# Final_NOEC_KosikC.net
KiCad netlist of a schematic drawn in EAGLE
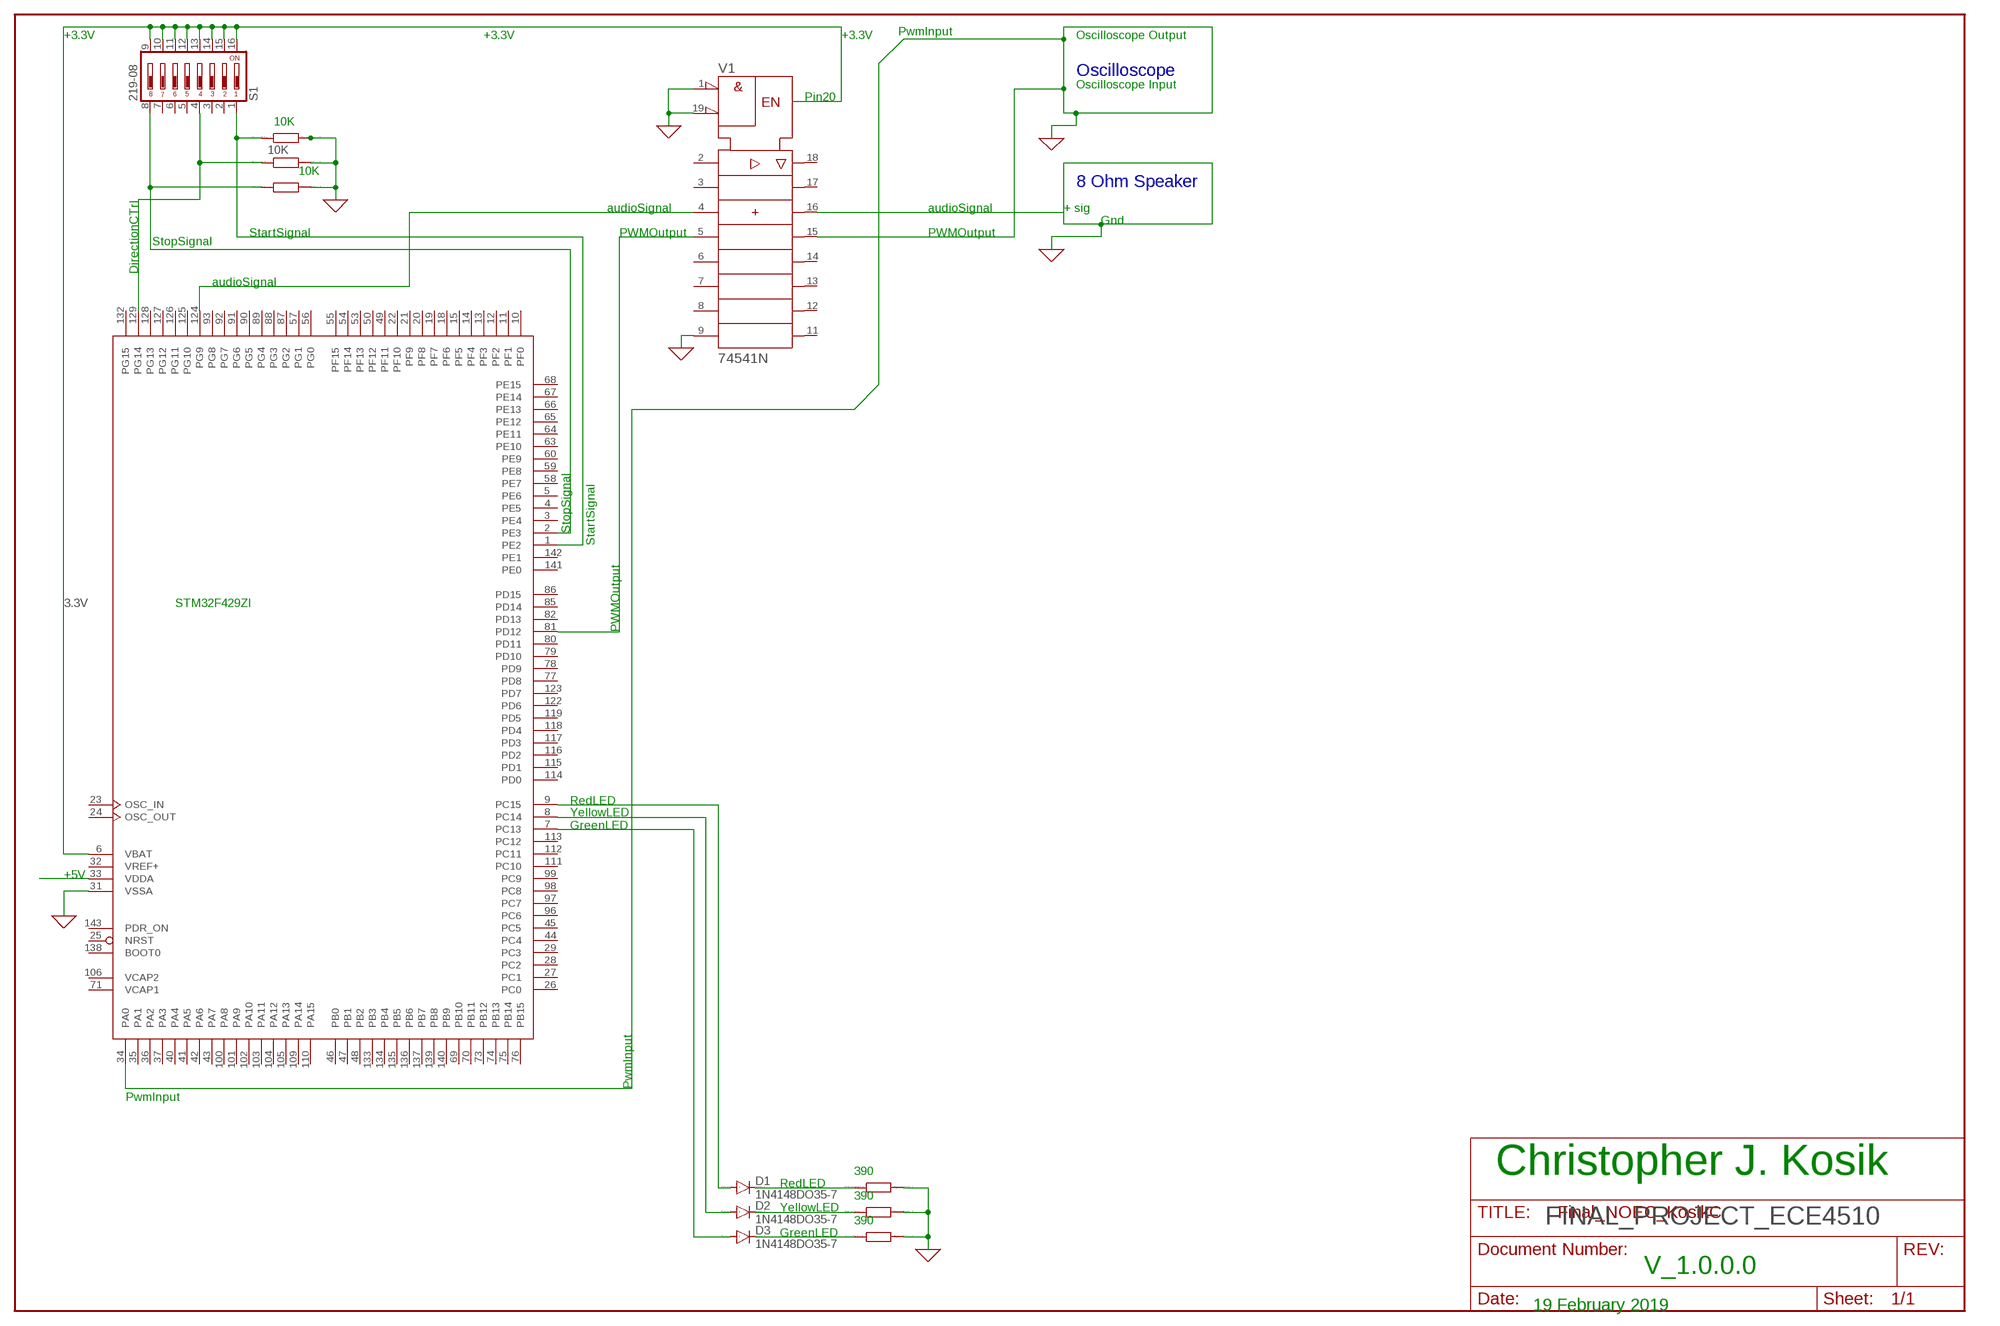
[diagram p0: schematic, sheet 1]

(export (version "E")
  (design (tool "Eeschema 10.0.6"))
  (components
    (comp (ref "D1")
      (value "1N4148DO35-7")
      (footprint "eagle-import:DO35-7")
      (libsource (lib "eagle-import") (part "1N4148DO35-7"))
    )
    (comp (ref "D2")
      (value "1N4148DO35-7")
      (footprint "eagle-import:DO35-7")
      (libsource (lib "eagle-import") (part "1N4148DO35-7"))
    )
    (comp (ref "D3")
      (value "1N4148DO35-7")
      (footprint "eagle-import:DO35-7")
      (libsource (lib "eagle-import") (part "1N4148DO35-7"))
    )
    (comp (ref "IC1")
      (value "STM32F429ZGT")
      (footprint "eagle-import:LQFP144")
      (libsource (lib "eagle-import") (part "STM32F429ZTG"))
    )
    (comp (ref "R1")
      (value "10K")
      (footprint "eagle-import:R0805")
      (libsource (lib "eagle-import") (part "R"))
    )
    (comp (ref "R2") (value "R") (footprint "eagle-import:R0805") (libsource (lib "eagle-import") (part "R")))
    (comp (ref "R3") (value "R") (footprint "eagle-import:R0805") (libsource (lib "eagle-import") (part "R")))
    (comp (ref "R4") (value "R") (footprint "eagle-import:R0805") (libsource (lib "eagle-import") (part "R")))
    (comp (ref "R5") (value "R") (footprint "eagle-import:R0805") (libsource (lib "eagle-import") (part "R")))
    (comp (ref "R6") (value "R") (footprint "eagle-import:R0805") (libsource (lib "eagle-import") (part "R")))
    (comp (ref "S1")
      (value "219-08")
      (footprint "eagle-import:CTS-219-08")
      (libsource (lib "eagle-import") (part "219-08"))
    )
    (comp (ref "V1")
      (value "74541N")
      (footprint "eagle-import:DIL20")
      (libsource (lib "eagle-import") (part "74541N"))
    )
  )
  (nets
    (net (code "1") (name "/3.3V") (class "Default")
      (node (ref "IC1") (pin "6") (pinfunction "VBAT_6") (pintype "power_in"))
      (node (ref "S1") (pin "10") (pinfunction "10_10") (pintype "passive"))
      (node (ref "S1") (pin "11") (pinfunction "11_11") (pintype "passive"))
      (node (ref "S1") (pin "12") (pinfunction "12_12") (pintype "passive"))
      (node (ref "S1") (pin "13") (pinfunction "13_13") (pintype "passive"))
      (node (ref "S1") (pin "14") (pinfunction "14_14") (pintype "passive"))
      (node (ref "S1") (pin "15") (pinfunction "15_15") (pintype "passive"))
      (node (ref "S1") (pin "16") (pinfunction "16_16") (pintype "passive"))
      (node (ref "S1") (pin "9") (pinfunction "9_9") (pintype "passive"))
    )
    (net (code "2") (name "/VCAP1") (class "Default")
      (node (ref "IC1") (pin "71") (pinfunction "VCAP1_71") (pintype "power_in"))
    )
    (net (code "3") (name "/VCAP2") (class "Default")
      (node (ref "IC1") (pin "106") (pinfunction "VCAP2_106") (pintype "power_in"))
    )
    (net (code "4") (name "/VREF+") (class "Default")
      (node (ref "IC1") (pin "32") (pinfunction "VREF+_32") (pintype "power_in"))
    )
    (net (code "5") (name "GND") (class "Default")
      (node (ref "IC1") (pin "31") (pinfunction "VSSA_31") (pintype "power_in"))
      (node (ref "IC1") (pin "34") (pinfunction "PA0_34") (pintype "bidirectional"))
      (node (ref "R1") (pin "2") (pinfunction "2_2") (pintype "passive"))
      (node (ref "R2") (pin "2") (pinfunction "2_2") (pintype "passive"))
      (node (ref "R3") (pin "2") (pinfunction "2_2") (pintype "passive"))
      (node (ref "R4") (pin "2") (pinfunction "2_2") (pintype "passive"))
      (node (ref "R5") (pin "2") (pinfunction "2_2") (pintype "passive"))
      (node (ref "R6") (pin "2") (pinfunction "2_2") (pintype "passive"))
      (node (ref "V1") (pin "1") (pinfunction "~{G1}_1") (pintype "input"))
      (node (ref "V1") (pin "15") (pinfunction "Y4_15") (pintype "tri_state"))
      (node (ref "V1") (pin "16") (pinfunction "Y3_16") (pintype "tri_state"))
      (node (ref "V1") (pin "19") (pinfunction "~{G2}_19") (pintype "input"))
      (node (ref "V1") (pin "9") (pinfunction "A8_9") (pintype "input"))
    )
    (net (code "6") (name "Net-(D1-PadC)") (class "Default")
      (node (ref "D1") (pin "C") (pinfunction "C_C") (pintype "passive"))
      (node (ref "R4") (pin "1") (pinfunction "1_1") (pintype "passive"))
    )
    (net (code "7") (name "Net-(D2-PadC)") (class "Default")
      (node (ref "D2") (pin "C") (pinfunction "C_C") (pintype "passive"))
      (node (ref "R5") (pin "1") (pinfunction "1_1") (pintype "passive"))
    )
    (net (code "8") (name "Net-(D3-PadC)") (class "Default")
      (node (ref "D3") (pin "C") (pinfunction "C_C") (pintype "passive"))
      (node (ref "R6") (pin "1") (pinfunction "1_1") (pintype "passive"))
    )
    (net (code "9") (name "Net-(IC1A-PC13)") (class "Default")
      (node (ref "D3") (pin "A") (pinfunction "A_A") (pintype "passive"))
      (node (ref "IC1") (pin "7") (pinfunction "PC13_7") (pintype "bidirectional"))
    )
    (net (code "10") (name "Net-(IC1A-PC14)") (class "Default")
      (node (ref "D2") (pin "A") (pinfunction "A_A") (pintype "passive"))
      (node (ref "IC1") (pin "8") (pinfunction "PC14_8") (pintype "bidirectional"))
    )
    (net (code "11") (name "Net-(IC1A-PC15)") (class "Default")
      (node (ref "D1") (pin "A") (pinfunction "A_A") (pintype "passive"))
      (node (ref "IC1") (pin "9") (pinfunction "PC15_9") (pintype "bidirectional"))
    )
    (net (code "12") (name "Net-(IC1A-PD12)") (class "Default")
      (node (ref "IC1") (pin "81") (pinfunction "PD12_81") (pintype "bidirectional"))
      (node (ref "V1") (pin "5") (pinfunction "A4_5") (pintype "input"))
    )
    (net (code "13") (name "Net-(IC1A-PE2)") (class "Default")
      (node (ref "IC1") (pin "1") (pinfunction "PE2_1") (pintype "bidirectional"))
      (node (ref "R1") (pin "1") (pinfunction "1_1") (pintype "passive"))
      (node (ref "S1") (pin "1") (pinfunction "1_1") (pintype "passive"))
    )
    (net (code "14") (name "Net-(IC1A-PE3)") (class "Default")
      (node (ref "IC1") (pin "2") (pinfunction "PE3_2") (pintype "bidirectional"))
      (node (ref "R3") (pin "1") (pinfunction "1_1") (pintype "passive"))
      (node (ref "S1") (pin "8") (pinfunction "8_8") (pintype "passive"))
    )
    (net (code "15") (name "Net-(IC1A-PG9)") (class "Default")
      (node (ref "IC1") (pin "124") (pinfunction "PG9_124") (pintype "bidirectional"))
      (node (ref "V1") (pin "4") (pinfunction "A3_4") (pintype "input"))
    )
    (net (code "16") (name "Net-(IC1A-PG14)") (class "Default")
      (node (ref "IC1") (pin "129") (pinfunction "PG14_129") (pintype "bidirectional"))
      (node (ref "R2") (pin "1") (pinfunction "1_1") (pintype "passive"))
      (node (ref "S1") (pin "4") (pinfunction "4_4") (pintype "passive"))
    )
    (net (code "17") (name "unconnected-(IC1A-BOOT0-Pad138)") (class "Default")
      (node (ref "IC1") (pin "138") (pinfunction "BOOT0_138") (pintype "input"))
    )
    (net (code "18") (name "unconnected-(IC1A-NRST-Pad25)") (class "Default")
      (node (ref "IC1") (pin "25") (pinfunction "NRST_25") (pintype "bidirectional"))
    )
    (net (code "19") (name "unconnected-(IC1A-OSC_IN-Pad23)") (class "Default")
      (node (ref "IC1") (pin "23") (pinfunction "OSC_IN_23") (pintype "bidirectional"))
    )
    (net (code "20") (name "unconnected-(IC1A-OSC_OUT-Pad24)") (class "Default")
      (node (ref "IC1") (pin "24") (pinfunction "OSC_OUT_24") (pintype "bidirectional"))
    )
    (net (code "21") (name "unconnected-(IC1A-PA1-Pad35)") (class "Default")
      (node (ref "IC1") (pin "35") (pinfunction "PA1_35") (pintype "bidirectional"))
    )
    (net (code "22") (name "unconnected-(IC1A-PA2-Pad36)") (class "Default")
      (node (ref "IC1") (pin "36") (pinfunction "PA2_36") (pintype "bidirectional"))
    )
    (net (code "23") (name "unconnected-(IC1A-PA3-Pad37)") (class "Default")
      (node (ref "IC1") (pin "37") (pinfunction "PA3_37") (pintype "bidirectional"))
    )
    (net (code "24") (name "unconnected-(IC1A-PA4-Pad40)") (class "Default")
      (node (ref "IC1") (pin "40") (pinfunction "PA4_40") (pintype "bidirectional"))
    )
    (net (code "25") (name "unconnected-(IC1A-PA5-Pad41)") (class "Default")
      (node (ref "IC1") (pin "41") (pinfunction "PA5_41") (pintype "bidirectional"))
    )
    (net (code "26") (name "unconnected-(IC1A-PA6-Pad42)") (class "Default")
      (node (ref "IC1") (pin "42") (pinfunction "PA6_42") (pintype "bidirectional"))
    )
    (net (code "27") (name "unconnected-(IC1A-PA7-Pad43)") (class "Default")
      (node (ref "IC1") (pin "43") (pinfunction "PA7_43") (pintype "bidirectional"))
    )
    (net (code "28") (name "unconnected-(IC1A-PA8-Pad100)") (class "Default")
      (node (ref "IC1") (pin "100") (pinfunction "PA8_100") (pintype "bidirectional"))
    )
    (net (code "29") (name "unconnected-(IC1A-PA9-Pad101)") (class "Default")
      (node (ref "IC1") (pin "101") (pinfunction "PA9_101") (pintype "bidirectional"))
    )
    (net (code "30") (name "unconnected-(IC1A-PA10-Pad102)") (class "Default")
      (node (ref "IC1") (pin "102") (pinfunction "PA10_102") (pintype "bidirectional"))
    )
    (net (code "31") (name "unconnected-(IC1A-PA11-Pad103)") (class "Default")
      (node (ref "IC1") (pin "103") (pinfunction "PA11_103") (pintype "bidirectional"))
    )
    (net (code "32") (name "unconnected-(IC1A-PA12-Pad104)") (class "Default")
      (node (ref "IC1") (pin "104") (pinfunction "PA12_104") (pintype "bidirectional"))
    )
    (net (code "33") (name "unconnected-(IC1A-PA13-Pad105)") (class "Default")
      (node (ref "IC1") (pin "105") (pinfunction "PA13_105") (pintype "bidirectional"))
    )
    (net (code "34") (name "unconnected-(IC1A-PA14-Pad109)") (class "Default")
      (node (ref "IC1") (pin "109") (pinfunction "PA14_109") (pintype "bidirectional"))
    )
    (net (code "35") (name "unconnected-(IC1A-PA15-Pad110)") (class "Default")
      (node (ref "IC1") (pin "110") (pinfunction "PA15_110") (pintype "bidirectional"))
    )
    (net (code "36") (name "unconnected-(IC1A-PB0-Pad46)") (class "Default")
      (node (ref "IC1") (pin "46") (pinfunction "PB0_46") (pintype "bidirectional"))
    )
    (net (code "37") (name "unconnected-(IC1A-PB1-Pad47)") (class "Default")
      (node (ref "IC1") (pin "47") (pinfunction "PB1_47") (pintype "bidirectional"))
    )
    (net (code "38") (name "unconnected-(IC1A-PB2-Pad48)") (class "Default")
      (node (ref "IC1") (pin "48") (pinfunction "PB2_48") (pintype "bidirectional"))
    )
    (net (code "39") (name "unconnected-(IC1A-PB3-Pad133)") (class "Default")
      (node (ref "IC1") (pin "133") (pinfunction "PB3_133") (pintype "bidirectional"))
    )
    (net (code "40") (name "unconnected-(IC1A-PB4-Pad134)") (class "Default")
      (node (ref "IC1") (pin "134") (pinfunction "PB4_134") (pintype "bidirectional"))
    )
    (net (code "41") (name "unconnected-(IC1A-PB5-Pad135)") (class "Default")
      (node (ref "IC1") (pin "135") (pinfunction "PB5_135") (pintype "bidirectional"))
    )
    (net (code "42") (name "unconnected-(IC1A-PB6-Pad136)") (class "Default")
      (node (ref "IC1") (pin "136") (pinfunction "PB6_136") (pintype "bidirectional"))
    )
    (net (code "43") (name "unconnected-(IC1A-PB7-Pad137)") (class "Default")
      (node (ref "IC1") (pin "137") (pinfunction "PB7_137") (pintype "bidirectional"))
    )
    (net (code "44") (name "unconnected-(IC1A-PB8-Pad139)") (class "Default")
      (node (ref "IC1") (pin "139") (pinfunction "PB8_139") (pintype "bidirectional"))
    )
    (net (code "45") (name "unconnected-(IC1A-PB9-Pad140)") (class "Default")
      (node (ref "IC1") (pin "140") (pinfunction "PB9_140") (pintype "bidirectional"))
    )
    (net (code "46") (name "unconnected-(IC1A-PB10-Pad69)") (class "Default")
      (node (ref "IC1") (pin "69") (pinfunction "PB10_69") (pintype "bidirectional"))
    )
    (net (code "47") (name "unconnected-(IC1A-PB11-Pad70)") (class "Default")
      (node (ref "IC1") (pin "70") (pinfunction "PB11_70") (pintype "bidirectional"))
    )
    (net (code "48") (name "unconnected-(IC1A-PB12-Pad73)") (class "Default")
      (node (ref "IC1") (pin "73") (pinfunction "PB12_73") (pintype "bidirectional"))
    )
    (net (code "49") (name "unconnected-(IC1A-PB13-Pad74)") (class "Default")
      (node (ref "IC1") (pin "74") (pinfunction "PB13_74") (pintype "bidirectional"))
    )
    (net (code "50") (name "unconnected-(IC1A-PB14-Pad75)") (class "Default")
      (node (ref "IC1") (pin "75") (pinfunction "PB14_75") (pintype "bidirectional"))
    )
    (net (code "51") (name "unconnected-(IC1A-PB15-Pad76)") (class "Default")
      (node (ref "IC1") (pin "76") (pinfunction "PB15_76") (pintype "bidirectional"))
    )
    (net (code "52") (name "unconnected-(IC1A-PC0-Pad26)") (class "Default")
      (node (ref "IC1") (pin "26") (pinfunction "PC0_26") (pintype "bidirectional"))
    )
    (net (code "53") (name "unconnected-(IC1A-PC1-Pad27)") (class "Default")
      (node (ref "IC1") (pin "27") (pinfunction "PC1_27") (pintype "bidirectional"))
    )
    (net (code "54") (name "unconnected-(IC1A-PC2-Pad28)") (class "Default")
      (node (ref "IC1") (pin "28") (pinfunction "PC2_28") (pintype "bidirectional"))
    )
    (net (code "55") (name "unconnected-(IC1A-PC3-Pad29)") (class "Default")
      (node (ref "IC1") (pin "29") (pinfunction "PC3_29") (pintype "bidirectional"))
    )
    (net (code "56") (name "unconnected-(IC1A-PC4-Pad44)") (class "Default")
      (node (ref "IC1") (pin "44") (pinfunction "PC4_44") (pintype "bidirectional"))
    )
    (net (code "57") (name "unconnected-(IC1A-PC5-Pad45)") (class "Default")
      (node (ref "IC1") (pin "45") (pinfunction "PC5_45") (pintype "bidirectional"))
    )
    (net (code "58") (name "unconnected-(IC1A-PC6-Pad96)") (class "Default")
      (node (ref "IC1") (pin "96") (pinfunction "PC6_96") (pintype "bidirectional"))
    )
    (net (code "59") (name "unconnected-(IC1A-PC7-Pad97)") (class "Default")
      (node (ref "IC1") (pin "97") (pinfunction "PC7_97") (pintype "bidirectional"))
    )
    (net (code "60") (name "unconnected-(IC1A-PC8-Pad98)") (class "Default")
      (node (ref "IC1") (pin "98") (pinfunction "PC8_98") (pintype "bidirectional"))
    )
    (net (code "61") (name "unconnected-(IC1A-PC9-Pad99)") (class "Default")
      (node (ref "IC1") (pin "99") (pinfunction "PC9_99") (pintype "bidirectional"))
    )
    (net (code "62") (name "unconnected-(IC1A-PC10-Pad111)") (class "Default")
      (node (ref "IC1") (pin "111") (pinfunction "PC10_111") (pintype "bidirectional"))
    )
    (net (code "63") (name "unconnected-(IC1A-PC11-Pad112)") (class "Default")
      (node (ref "IC1") (pin "112") (pinfunction "PC11_112") (pintype "bidirectional"))
    )
    (net (code "64") (name "unconnected-(IC1A-PC12-Pad113)") (class "Default")
      (node (ref "IC1") (pin "113") (pinfunction "PC12_113") (pintype "bidirectional"))
    )
    (net (code "65") (name "unconnected-(IC1A-PD0-Pad114)") (class "Default")
      (node (ref "IC1") (pin "114") (pinfunction "PD0_114") (pintype "bidirectional"))
    )
    (net (code "66") (name "unconnected-(IC1A-PD1-Pad115)") (class "Default")
      (node (ref "IC1") (pin "115") (pinfunction "PD1_115") (pintype "bidirectional"))
    )
    (net (code "67") (name "unconnected-(IC1A-PD2-Pad116)") (class "Default")
      (node (ref "IC1") (pin "116") (pinfunction "PD2_116") (pintype "bidirectional"))
    )
    (net (code "68") (name "unconnected-(IC1A-PD3-Pad117)") (class "Default")
      (node (ref "IC1") (pin "117") (pinfunction "PD3_117") (pintype "bidirectional"))
    )
    (net (code "69") (name "unconnected-(IC1A-PD4-Pad118)") (class "Default")
      (node (ref "IC1") (pin "118") (pinfunction "PD4_118") (pintype "bidirectional"))
    )
    (net (code "70") (name "unconnected-(IC1A-PD5-Pad119)") (class "Default")
      (node (ref "IC1") (pin "119") (pinfunction "PD5_119") (pintype "bidirectional"))
    )
    (net (code "71") (name "unconnected-(IC1A-PD6-Pad122)") (class "Default")
      (node (ref "IC1") (pin "122") (pinfunction "PD6_122") (pintype "bidirectional"))
    )
    (net (code "72") (name "unconnected-(IC1A-PD7-Pad123)") (class "Default")
      (node (ref "IC1") (pin "123") (pinfunction "PD7_123") (pintype "bidirectional"))
    )
    (net (code "73") (name "unconnected-(IC1A-PD8-Pad77)") (class "Default")
      (node (ref "IC1") (pin "77") (pinfunction "PD8_77") (pintype "bidirectional"))
    )
    (net (code "74") (name "unconnected-(IC1A-PD9-Pad78)") (class "Default")
      (node (ref "IC1") (pin "78") (pinfunction "PD9_78") (pintype "bidirectional"))
    )
    (net (code "75") (name "unconnected-(IC1A-PD10-Pad79)") (class "Default")
      (node (ref "IC1") (pin "79") (pinfunction "PD10_79") (pintype "bidirectional"))
    )
    (net (code "76") (name "unconnected-(IC1A-PD11-Pad80)") (class "Default")
      (node (ref "IC1") (pin "80") (pinfunction "PD11_80") (pintype "bidirectional"))
    )
    (net (code "77") (name "unconnected-(IC1A-PD13-Pad82)") (class "Default")
      (node (ref "IC1") (pin "82") (pinfunction "PD13_82") (pintype "bidirectional"))
    )
    (net (code "78") (name "unconnected-(IC1A-PD14-Pad85)") (class "Default")
      (node (ref "IC1") (pin "85") (pinfunction "PD14_85") (pintype "bidirectional"))
    )
    (net (code "79") (name "unconnected-(IC1A-PD15-Pad86)") (class "Default")
      (node (ref "IC1") (pin "86") (pinfunction "PD15_86") (pintype "bidirectional"))
    )
    (net (code "80") (name "unconnected-(IC1A-PDR_ON-Pad143)") (class "Default")
      (node (ref "IC1") (pin "143") (pinfunction "PDR_ON_143") (pintype "input"))
    )
    (net (code "81") (name "unconnected-(IC1A-PE0-Pad141)") (class "Default")
      (node (ref "IC1") (pin "141") (pinfunction "PE0_141") (pintype "bidirectional"))
    )
    (net (code "82") (name "unconnected-(IC1A-PE1-Pad142)") (class "Default")
      (node (ref "IC1") (pin "142") (pinfunction "PE1_142") (pintype "bidirectional"))
    )
    (net (code "83") (name "unconnected-(IC1A-PE4-Pad3)") (class "Default")
      (node (ref "IC1") (pin "3") (pinfunction "PE4_3") (pintype "bidirectional"))
    )
    (net (code "84") (name "unconnected-(IC1A-PE5-Pad4)") (class "Default")
      (node (ref "IC1") (pin "4") (pinfunction "PE5_4") (pintype "bidirectional"))
    )
    (net (code "85") (name "unconnected-(IC1A-PE6-Pad5)") (class "Default")
      (node (ref "IC1") (pin "5") (pinfunction "PE6_5") (pintype "bidirectional"))
    )
    (net (code "86") (name "unconnected-(IC1A-PE7-Pad58)") (class "Default")
      (node (ref "IC1") (pin "58") (pinfunction "PE7_58") (pintype "bidirectional"))
    )
    (net (code "87") (name "unconnected-(IC1A-PE8-Pad59)") (class "Default")
      (node (ref "IC1") (pin "59") (pinfunction "PE8_59") (pintype "bidirectional"))
    )
    (net (code "88") (name "unconnected-(IC1A-PE9-Pad60)") (class "Default")
      (node (ref "IC1") (pin "60") (pinfunction "PE9_60") (pintype "bidirectional"))
    )
    (net (code "89") (name "unconnected-(IC1A-PE10-Pad63)") (class "Default")
      (node (ref "IC1") (pin "63") (pinfunction "PE10_63") (pintype "bidirectional"))
    )
    (net (code "90") (name "unconnected-(IC1A-PE11-Pad64)") (class "Default")
      (node (ref "IC1") (pin "64") (pinfunction "PE11_64") (pintype "bidirectional"))
    )
    (net (code "91") (name "unconnected-(IC1A-PE12-Pad65)") (class "Default")
      (node (ref "IC1") (pin "65") (pinfunction "PE12_65") (pintype "bidirectional"))
    )
    (net (code "92") (name "unconnected-(IC1A-PE13-Pad66)") (class "Default")
      (node (ref "IC1") (pin "66") (pinfunction "PE13_66") (pintype "bidirectional"))
    )
    (net (code "93") (name "unconnected-(IC1A-PE14-Pad67)") (class "Default")
      (node (ref "IC1") (pin "67") (pinfunction "PE14_67") (pintype "bidirectional"))
    )
    (net (code "94") (name "unconnected-(IC1A-PE15-Pad68)") (class "Default")
      (node (ref "IC1") (pin "68") (pinfunction "PE15_68") (pintype "bidirectional"))
    )
    (net (code "95") (name "unconnected-(IC1A-PF0-Pad10)") (class "Default")
      (node (ref "IC1") (pin "10") (pinfunction "PF0_10") (pintype "bidirectional"))
    )
    (net (code "96") (name "unconnected-(IC1A-PF1-Pad11)") (class "Default")
      (node (ref "IC1") (pin "11") (pinfunction "PF1_11") (pintype "bidirectional"))
    )
    (net (code "97") (name "unconnected-(IC1A-PF2-Pad12)") (class "Default")
      (node (ref "IC1") (pin "12") (pinfunction "PF2_12") (pintype "bidirectional"))
    )
    (net (code "98") (name "unconnected-(IC1A-PF3-Pad13)") (class "Default")
      (node (ref "IC1") (pin "13") (pinfunction "PF3_13") (pintype "bidirectional"))
    )
    (net (code "99") (name "unconnected-(IC1A-PF4-Pad14)") (class "Default")
      (node (ref "IC1") (pin "14") (pinfunction "PF4_14") (pintype "bidirectional"))
    )
    (net (code "100") (name "unconnected-(IC1A-PF5-Pad15)") (class "Default")
      (node (ref "IC1") (pin "15") (pinfunction "PF5_15") (pintype "bidirectional"))
    )
    (net (code "101") (name "unconnected-(IC1A-PF6-Pad18)") (class "Default")
      (node (ref "IC1") (pin "18") (pinfunction "PF6_18") (pintype "bidirectional"))
    )
    (net (code "102") (name "unconnected-(IC1A-PF7-Pad19)") (class "Default")
      (node (ref "IC1") (pin "19") (pinfunction "PF7_19") (pintype "bidirectional"))
    )
    (net (code "103") (name "unconnected-(IC1A-PF8-Pad20)") (class "Default")
      (node (ref "IC1") (pin "20") (pinfunction "PF8_20") (pintype "bidirectional"))
    )
    (net (code "104") (name "unconnected-(IC1A-PF9-Pad21)") (class "Default")
      (node (ref "IC1") (pin "21") (pinfunction "PF9_21") (pintype "bidirectional"))
    )
    (net (code "105") (name "unconnected-(IC1A-PF10-Pad22)") (class "Default")
      (node (ref "IC1") (pin "22") (pinfunction "PF10_22") (pintype "bidirectional"))
    )
    (net (code "106") (name "unconnected-(IC1A-PF11-Pad49)") (class "Default")
      (node (ref "IC1") (pin "49") (pinfunction "PF11_49") (pintype "bidirectional"))
    )
    (net (code "107") (name "unconnected-(IC1A-PF12-Pad50)") (class "Default")
      (node (ref "IC1") (pin "50") (pinfunction "PF12_50") (pintype "bidirectional"))
    )
    (net (code "108") (name "unconnected-(IC1A-PF13-Pad53)") (class "Default")
      (node (ref "IC1") (pin "53") (pinfunction "PF13_53") (pintype "bidirectional"))
    )
    (net (code "109") (name "unconnected-(IC1A-PF14-Pad54)") (class "Default")
      (node (ref "IC1") (pin "54") (pinfunction "PF14_54") (pintype "bidirectional"))
    )
    (net (code "110") (name "unconnected-(IC1A-PF15-Pad55)") (class "Default")
      (node (ref "IC1") (pin "55") (pinfunction "PF15_55") (pintype "bidirectional"))
    )
    (net (code "111") (name "unconnected-(IC1A-PG0-Pad56)") (class "Default")
      (node (ref "IC1") (pin "56") (pinfunction "PG0_56") (pintype "bidirectional"))
    )
    (net (code "112") (name "unconnected-(IC1A-PG1-Pad57)") (class "Default")
      (node (ref "IC1") (pin "57") (pinfunction "PG1_57") (pintype "bidirectional"))
    )
    (net (code "113") (name "unconnected-(IC1A-PG2-Pad87)") (class "Default")
      (node (ref "IC1") (pin "87") (pinfunction "PG2_87") (pintype "bidirectional"))
    )
    (net (code "114") (name "unconnected-(IC1A-PG3-Pad88)") (class "Default")
      (node (ref "IC1") (pin "88") (pinfunction "PG3_88") (pintype "bidirectional"))
    )
    (net (code "115") (name "unconnected-(IC1A-PG4-Pad89)") (class "Default")
      (node (ref "IC1") (pin "89") (pinfunction "PG4_89") (pintype "bidirectional"))
    )
    (net (code "116") (name "unconnected-(IC1A-PG5-Pad90)") (class "Default")
      (node (ref "IC1") (pin "90") (pinfunction "PG5_90") (pintype "bidirectional"))
    )
    (net (code "117") (name "unconnected-(IC1A-PG6-Pad91)") (class "Default")
      (node (ref "IC1") (pin "91") (pinfunction "PG6_91") (pintype "bidirectional"))
    )
    (net (code "118") (name "unconnected-(IC1A-PG7-Pad92)") (class "Default")
      (node (ref "IC1") (pin "92") (pinfunction "PG7_92") (pintype "bidirectional"))
    )
    (net (code "119") (name "unconnected-(IC1A-PG8-Pad93)") (class "Default")
      (node (ref "IC1") (pin "93") (pinfunction "PG8_93") (pintype "bidirectional"))
    )
    (net (code "120") (name "unconnected-(IC1A-PG10-Pad125)") (class "Default")
      (node (ref "IC1") (pin "125") (pinfunction "PG10_125") (pintype "bidirectional"))
    )
    (net (code "121") (name "unconnected-(IC1A-PG11-Pad126)") (class "Default")
      (node (ref "IC1") (pin "126") (pinfunction "PG11_126") (pintype "bidirectional"))
    )
    (net (code "122") (name "unconnected-(IC1A-PG12-Pad127)") (class "Default")
      (node (ref "IC1") (pin "127") (pinfunction "PG12_127") (pintype "bidirectional"))
    )
    (net (code "123") (name "unconnected-(IC1A-PG13-Pad128)") (class "Default")
      (node (ref "IC1") (pin "128") (pinfunction "PG13_128") (pintype "bidirectional"))
    )
    (net (code "124") (name "unconnected-(IC1A-PG15-Pad132)") (class "Default")
      (node (ref "IC1") (pin "132") (pinfunction "PG15_132") (pintype "bidirectional"))
    )
    (net (code "125") (name "unconnected-(IC1A-VDDA-Pad33)") (class "Default")
      (node (ref "IC1") (pin "33") (pinfunction "VDDA_33") (pintype "power_in"))
    )
    (net (code "126") (name "unconnected-(S1-Pad2)") (class "Default")
      (node (ref "S1") (pin "2") (pinfunction "2_2") (pintype "passive"))
    )
    (net (code "127") (name "unconnected-(S1-Pad3)") (class "Default")
      (node (ref "S1") (pin "3") (pinfunction "3_3") (pintype "passive"))
    )
    (net (code "128") (name "unconnected-(S1-Pad5)") (class "Default")
      (node (ref "S1") (pin "5") (pinfunction "5_5") (pintype "passive"))
    )
    (net (code "129") (name "unconnected-(S1-Pad6)") (class "Default")
      (node (ref "S1") (pin "6") (pinfunction "6_6") (pintype "passive"))
    )
    (net (code "130") (name "unconnected-(S1-Pad7)") (class "Default")
      (node (ref "S1") (pin "7") (pinfunction "7_7") (pintype "passive"))
    )
    (net (code "131") (name "unconnected-(V1C-A1-Pad2)") (class "Default")
      (node (ref "V1") (pin "2") (pinfunction "A1_2") (pintype "input"))
    )
    (net (code "132") (name "unconnected-(V1C-A2-Pad3)") (class "Default")
      (node (ref "V1") (pin "3") (pinfunction "A2_3") (pintype "input"))
    )
    (net (code "133") (name "unconnected-(V1C-A5-Pad6)") (class "Default")
      (node (ref "V1") (pin "6") (pinfunction "A5_6") (pintype "input"))
    )
    (net (code "134") (name "unconnected-(V1C-A6-Pad7)") (class "Default")
      (node (ref "V1") (pin "7") (pinfunction "A6_7") (pintype "input"))
    )
    (net (code "135") (name "unconnected-(V1C-A7-Pad8)") (class "Default")
      (node (ref "V1") (pin "8") (pinfunction "A7_8") (pintype "input"))
    )
    (net (code "136") (name "unconnected-(V1C-Y1-Pad18)") (class "Default")
      (node (ref "V1") (pin "18") (pinfunction "Y1_18") (pintype "tri_state"))
    )
    (net (code "137") (name "unconnected-(V1C-Y2-Pad17)") (class "Default")
      (node (ref "V1") (pin "17") (pinfunction "Y2_17") (pintype "tri_state"))
    )
    (net (code "138") (name "unconnected-(V1C-Y5-Pad14)") (class "Default")
      (node (ref "V1") (pin "14") (pinfunction "Y5_14") (pintype "tri_state"))
    )
    (net (code "139") (name "unconnected-(V1C-Y6-Pad13)") (class "Default")
      (node (ref "V1") (pin "13") (pinfunction "Y6_13") (pintype "tri_state"))
    )
    (net (code "140") (name "unconnected-(V1C-Y7-Pad12)") (class "Default")
      (node (ref "V1") (pin "12") (pinfunction "Y7_12") (pintype "tri_state"))
    )
    (net (code "141") (name "unconnected-(V1C-Y8-Pad11)") (class "Default")
      (node (ref "V1") (pin "11") (pinfunction "Y8_11") (pintype "tri_state"))
    )
  )
)
